# DM2097_BootSel.net
KiCad netlist of a schematic drawn in Altium Designer
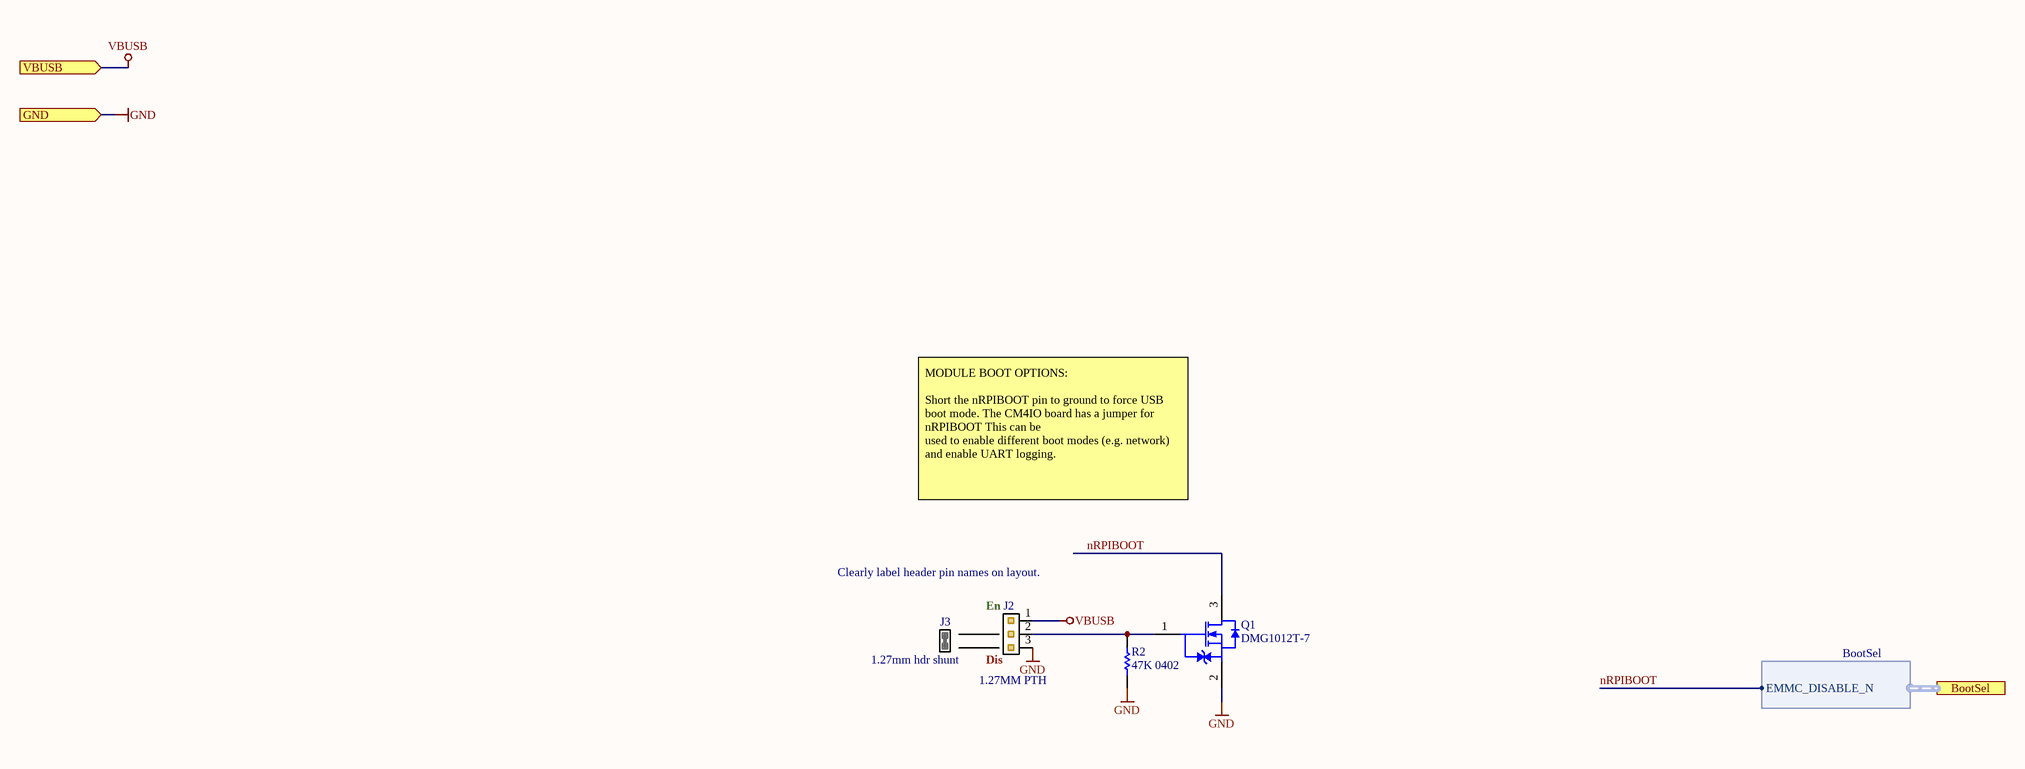
[diagram p0: DM2097_BootSel.SchDoc]

(export (version "E")
  (design (tool "Eeschema 10.0.6"))
  (components
    (comp (ref "J2")
      (value "1.27MM PTH")
      (footprint "LuxonisMaster:GRPB031VWVN-RC")
      (description "CONN HEADER VERT 3POS 1.27MM")
      (libsource (lib "LuxonisMaster") (part "GRPB031VWVN-RC"))
    )
    (comp (ref "J3")
      (value "1.27mm hdr shunt")
      (footprint "LuxonisMaster:M50-1900005")
      (description "CONN SHUNT 1.27MM BLACK")
      (libsource (lib "LuxonisMaster") (part "M50-1900005"))
    )
    (comp (ref "Q1")
      (value "DMG1012T-7")
      (footprint "LuxonisMaster:DMG1012T-7")
      (description "MOSFET N-CH 20V 630MA SOT-523")
      (libsource (lib "LuxonisMaster") (part "DMG1012T-7"))
    )
    (comp (ref "R2")
      (value "47K 0402")
      (footprint "RES_Altium_Vault_Generic:RESC0402(1005)_N")
      (description "RES SMD 47K OHM 1% 1/16W 0402")
      (fields (field (name "TOLERANCE") "1%"))
      (libsource (lib "LuxonisMaster") (part "RC0402FR-0747KL"))
    )
  )
  (nets
    (net (code "2") (name "/nRPIBOOT") (class "Default")
      (node (ref "Q1") (pin "3") (pinfunction "3_3") (pintype "passive"))
    )
    (net (code "4") (name "GND") (class "Default")
      (node (ref "J2") (pin "3") (pinfunction "3_3") (pintype "passive"))
      (node (ref "Q1") (pin "2") (pinfunction "2_2") (pintype "passive"))
      (node (ref "R2") (pin "1") (pinfunction "1_1") (pintype "passive"))
    )
    (net (code "5") (name "Net-(J2-Pad2)") (class "Default")
      (node (ref "J2") (pin "2") (pinfunction "2_2") (pintype "passive"))
      (node (ref "Q1") (pin "1") (pinfunction "1_1") (pintype "passive"))
      (node (ref "R2") (pin "2") (pinfunction "2_2") (pintype "passive"))
    )
    (net (code "6") (name "VBUSB") (class "Default")
      (node (ref "J2") (pin "1") (pinfunction "1_1") (pintype "passive"))
    )
  )
)
